# Main.net
KiCad netlist of a schematic drawn in Altium Designer
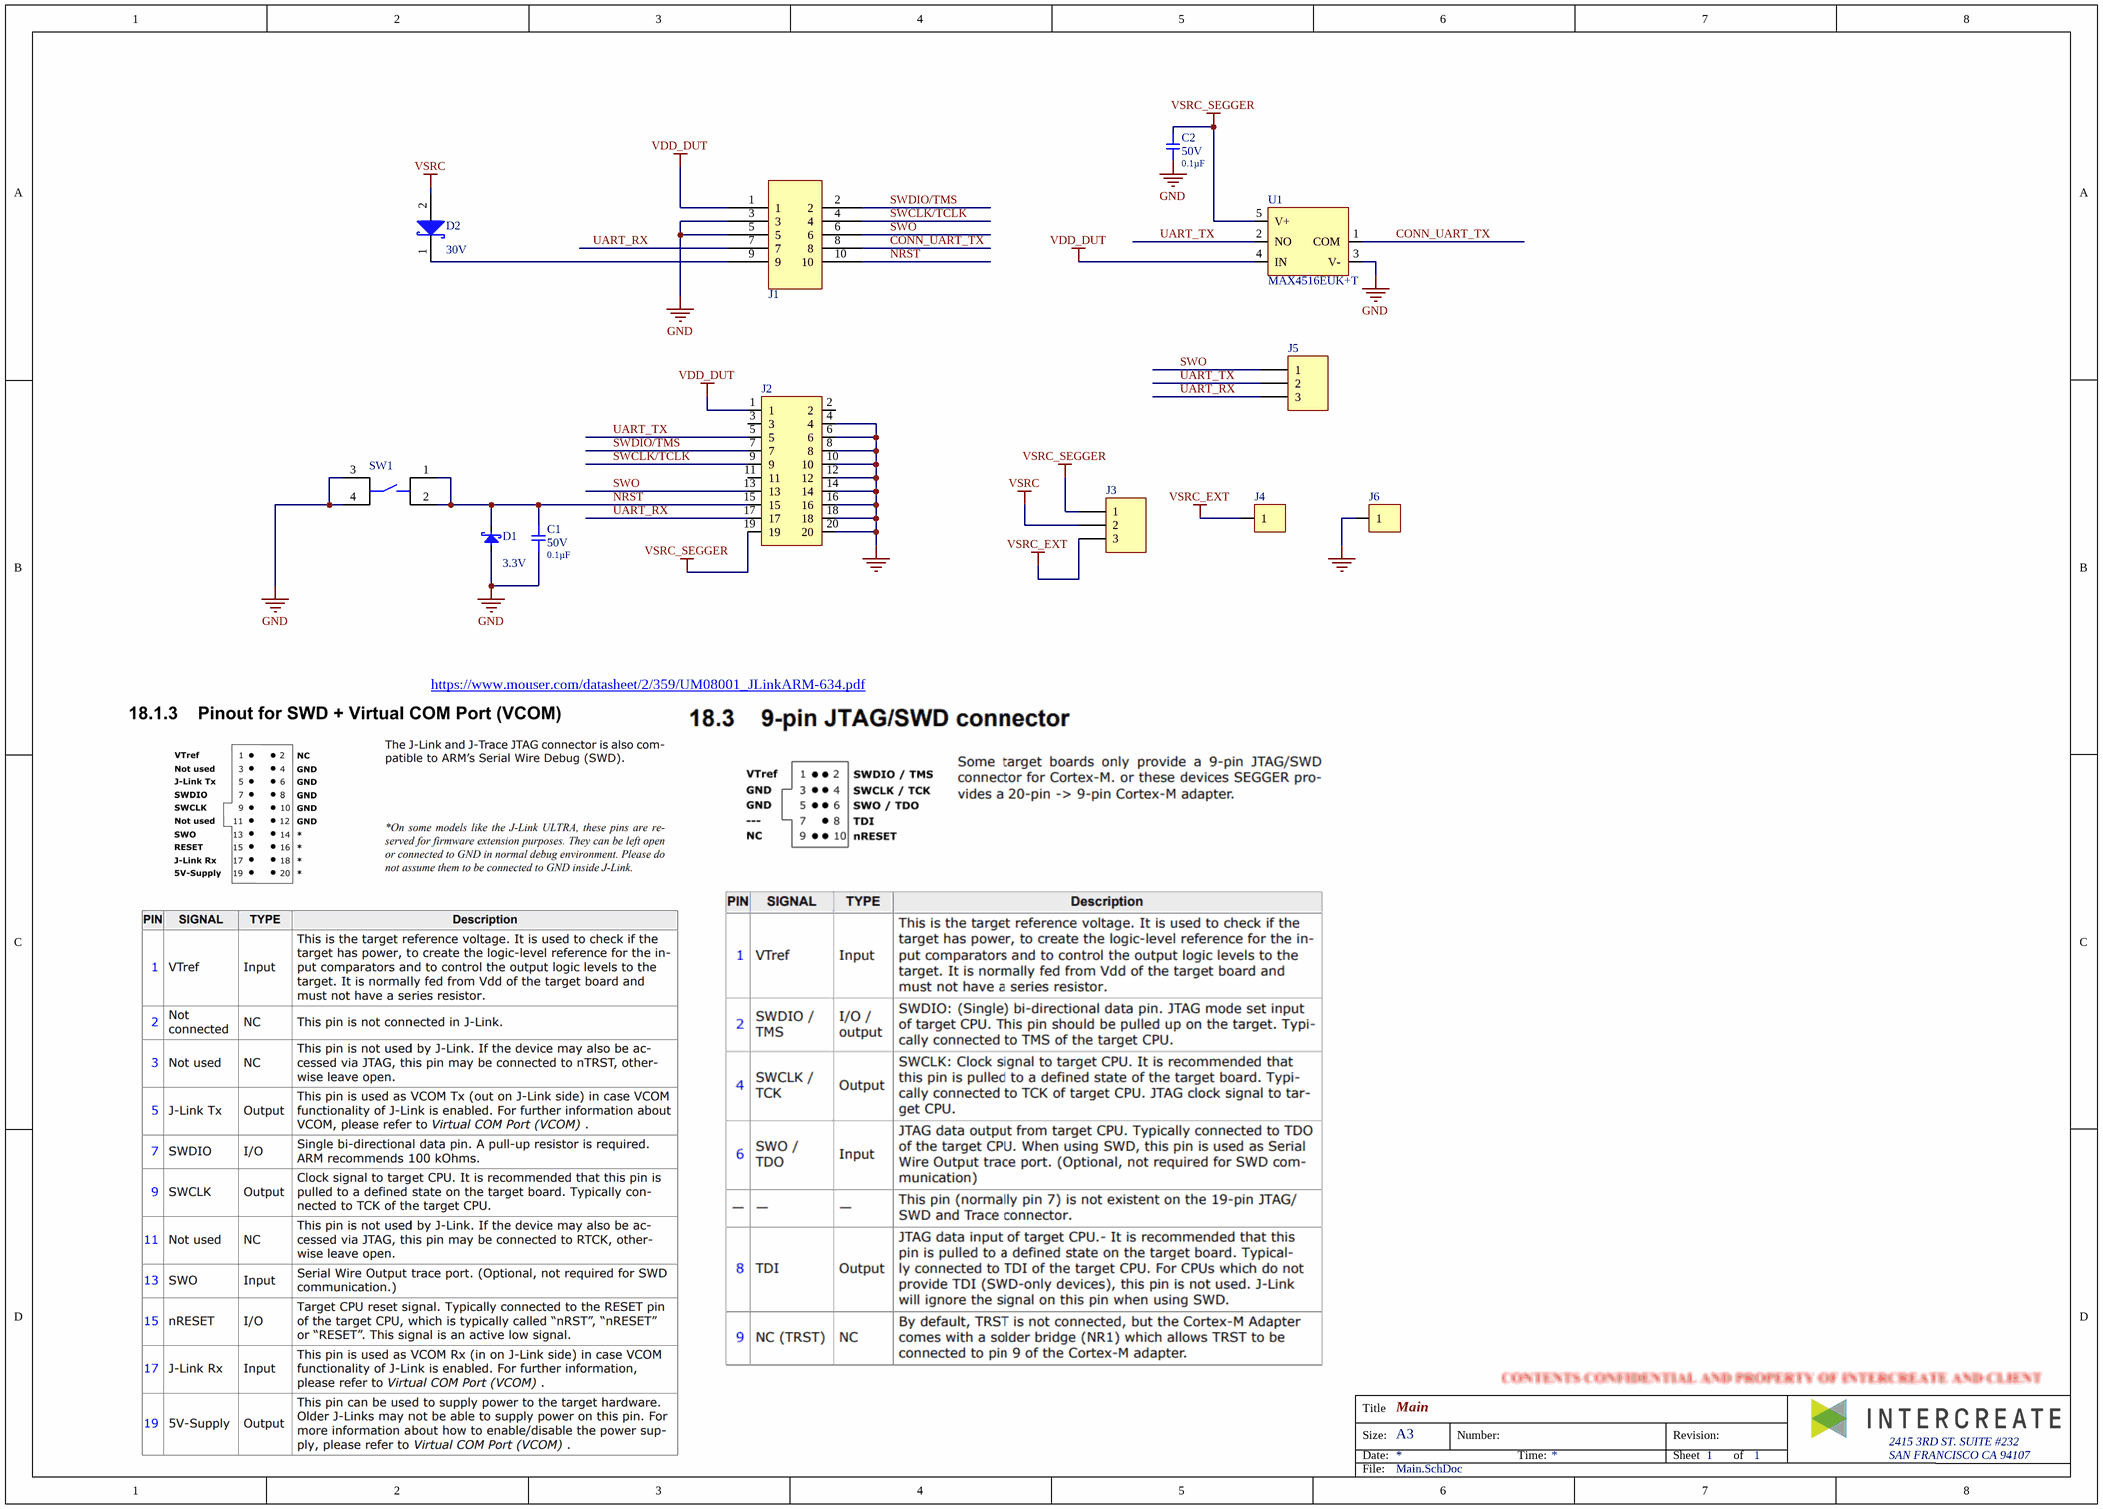
[diagram p0: Main.SchDoc]

(export (version "E")
  (design (tool "Eeschema 10.0.6"))
  (components
    (comp (ref "C1")
      (value "0.1µF")
      (footprint "CAP-0402")
      (description "CAP CER 0.1UF 50V X7R 0402 10%")
      (fields
        (field (name "TOLERANCE") "10%")
        (field (name "VOLTAGE RATING") "50V")
        (field (name "Comment") "GCM155R71H104KE02D")
      )
      (libsource (lib "intercreate") (part "CAP-0.1uF-50V-0402"))
    )
    (comp (ref "C2")
      (value "0.1µF")
      (footprint "CAP-0402")
      (description "CAP CER 0.1UF 50V X7R 0402 10%")
      (fields
        (field (name "TOLERANCE") "10%")
        (field (name "VOLTAGE RATING") "50V")
        (field (name "Comment") "GCM155R71H104KE02D")
      )
      (libsource (lib "intercreate") (part "CAP-0.1uF-50V-0402"))
    )
    (comp (ref "D1")
      (value "CPDQ3V3U-HF")
      (footprint "DIODE-SOD923f")
      (description "TVS DIODE 3.3V 10.4V SOD923F")
      (fields (field (name "REVERSE STANDOFF VOLTAGE") "3.3V"))
      (libsource (lib "intercreate") (part "DIODE-TVS-3.3V-SOD923F"))
    )
    (comp (ref "D2")
      (value "PMEG3010EP,115")
      (footprint "DIODE-SOD128")
      (description "DIODE SCHOTTKY 30V 1A SOD128")
      (fields (field (name "BASE PART NUMBER") "PMEG3010") (field (name "REVERSE VOLTAGE") "30V"))
      (libsource (lib "diodes") (part "DIODE-SCHOTTKY-30V-1A-SOD128"))
    )
    (comp (ref "J1")
      (value "FTSH-105-01-L-DV-K")
      (footprint "HDR-V-2X5-M")
      (description "CONN HEADER 10 POS DUAL .05\" SMD")
      (fields (field (name "MANUFACTURER") "Samtec"))
      (libsource (lib "intercreate") (part "HDR-V-2X5-M-JTAG"))
    )
    (comp (ref "J2")
      (value "SFH11-PBPC-D10-ST-BK")
      (footprint "HDR-V-2X10-F-2.54MM")
      (description "20 Position Header Connector 0.100\" (2.54mm) Through Hole Gold")
      (libsource (lib "intercreate") (part "HDR-V-2X10-F-2.54MM"))
    )
    (comp (ref "J3")
      (value "61300311121")
      (footprint "HDR-V-1X3")
      (description "Header, 3-Pin, 0.1\"")
      (fields (field (name "MANUFACTURER") "Wurth Electronics") (field (name "PUBLISHER") "Altium Limited"))
      (libsource (lib "intercreate") (part "HDR-V-1X3-M"))
    )
    (comp (ref "J4")
      (value "75160-101-01LF")
      (footprint "HDR-V-1X1-M")
      (libsource (lib "intercreate") (part "HDR-V-1X1-M"))
    )
    (comp (ref "J5")
      (value "61300311121")
      (footprint "HDR-V-1X3")
      (description "Header, 3-Pin, 0.1\"")
      (fields (field (name "MANUFACTURER") "Wurth Electronics") (field (name "PUBLISHER") "Altium Limited"))
      (libsource (lib "intercreate") (part "HDR-V-1X3-M"))
    )
    (comp (ref "J6")
      (value "75160-101-01LF")
      (footprint "HDR-V-1X1-M")
      (libsource (lib "intercreate") (part "HDR-V-1X1-M"))
    )
    (comp (ref "SW1")
      (value "PTS645SK50SMTR92 LFS")
      (footprint "BTN-SPST-PTS645SK50SMTR92")
      (description "C & K COMPONENTS - PTS645SK50SMTR92LFS - SWITCH, SPST, 0.05A, 12VDC, SMD, 5MM")
      (libsource (lib "intercreate") (part "BTN-SPST-PTS645SK50SMTR92"))
    )
    (comp (ref "U1")
      (value "MAX4516EUK+T")
      (footprint "IC-SOT-23-5")
      (description "MAX4516 Series SPST-NO 6V 20 Ohm SMT Analog Switch - SOT-23")
      (libsource (lib "intercreate") (part "IC-SW-MAX4516"))
    )
  )
  (nets
    (net (code "1") (name "/CONN_UART_TX") (class "Default")
      (node (ref "J1") (pin "8") (pinfunction "8_8") (pintype "passive"))
      (node (ref "U1") (pin "1") (pinfunction "COM_1") (pintype "passive"))
    )
    (net (code "2") (name "/NRST") (class "Default")
      (node (ref "C1") (pin "2") (pinfunction "2_2") (pintype "passive"))
      (node (ref "D1") (pin "1") (pinfunction "K_1") (pintype "passive"))
      (node (ref "J1") (pin "10") (pinfunction "10_10") (pintype "passive"))
      (node (ref "J2") (pin "15") (pinfunction "15_15") (pintype "passive"))
      (node (ref "SW1") (pin "1") (pinfunction "1_1") (pintype "passive"))
      (node (ref "SW1") (pin "2") (pinfunction "2_2") (pintype "passive"))
    )
    (net (code "3") (name "/SWCLK{slash}TCLK") (class "Default")
      (node (ref "J1") (pin "4") (pinfunction "4_4") (pintype "passive"))
      (node (ref "J2") (pin "9") (pinfunction "9_9") (pintype "passive"))
    )
    (net (code "4") (name "/SWDIO{slash}TMS") (class "Default")
      (node (ref "J1") (pin "2") (pinfunction "2_2") (pintype "passive"))
      (node (ref "J2") (pin "7") (pinfunction "7_7") (pintype "passive"))
    )
    (net (code "5") (name "/SWO") (class "Default")
      (node (ref "J1") (pin "6") (pinfunction "6_6") (pintype "passive"))
      (node (ref "J2") (pin "13") (pinfunction "13_13") (pintype "passive"))
      (node (ref "J5") (pin "1") (pinfunction "1_1") (pintype "passive"))
    )
    (net (code "6") (name "/UART_RX") (class "Default")
      (node (ref "J1") (pin "7") (pinfunction "7_7") (pintype "passive"))
      (node (ref "J2") (pin "17") (pinfunction "17_17") (pintype "passive"))
      (node (ref "J5") (pin "3") (pinfunction "3_3") (pintype "passive"))
    )
    (net (code "7") (name "/UART_TX") (class "Default")
      (node (ref "J2") (pin "5") (pinfunction "5_5") (pintype "passive"))
      (node (ref "J5") (pin "2") (pinfunction "2_2") (pintype "passive"))
      (node (ref "U1") (pin "2") (pinfunction "NO_2") (pintype "passive"))
    )
    (net (code "8") (name "GND") (class "Default")
      (node (ref "C1") (pin "1") (pinfunction "1_1") (pintype "passive"))
      (node (ref "C2") (pin "1") (pinfunction "1_1") (pintype "passive"))
      (node (ref "D1") (pin "2") (pinfunction "A_2") (pintype "passive"))
      (node (ref "J1") (pin "3") (pinfunction "3_3") (pintype "passive"))
      (node (ref "J1") (pin "5") (pinfunction "5_5") (pintype "passive"))
      (node (ref "J2") (pin "10") (pinfunction "10_10") (pintype "passive"))
      (node (ref "J2") (pin "12") (pinfunction "12_12") (pintype "passive"))
      (node (ref "J2") (pin "14") (pinfunction "14_14") (pintype "passive"))
      (node (ref "J2") (pin "16") (pinfunction "16_16") (pintype "passive"))
      (node (ref "J2") (pin "18") (pinfunction "18_18") (pintype "passive"))
      (node (ref "J2") (pin "20") (pinfunction "20_20") (pintype "passive"))
      (node (ref "J2") (pin "4") (pinfunction "4_4") (pintype "passive"))
      (node (ref "J2") (pin "6") (pinfunction "6_6") (pintype "passive"))
      (node (ref "J2") (pin "8") (pinfunction "8_8") (pintype "passive"))
      (node (ref "J6") (pin "1") (pinfunction "1_1") (pintype "passive"))
      (node (ref "SW1") (pin "3") (pinfunction "3_3") (pintype "passive"))
      (node (ref "SW1") (pin "4") (pinfunction "4_4") (pintype "passive"))
      (node (ref "U1") (pin "3") (pinfunction "V-_3") (pintype "passive"))
    )
    (net (code "9") (name "Net-(D2-K)") (class "Default")
      (node (ref "D2") (pin "1") (pinfunction "K_1") (pintype "passive"))
      (node (ref "J1") (pin "9") (pinfunction "9_9") (pintype "passive"))
    )
    (net (code "10") (name "VDD_DUT") (class "Default")
      (node (ref "J1") (pin "1") (pinfunction "1_1") (pintype "passive"))
      (node (ref "J2") (pin "1") (pinfunction "1_1") (pintype "passive"))
      (node (ref "U1") (pin "4") (pinfunction "IN_4") (pintype "passive"))
    )
    (net (code "11") (name "VSRC") (class "Default")
      (node (ref "D2") (pin "2") (pinfunction "A_2") (pintype "passive"))
      (node (ref "J3") (pin "2") (pinfunction "2_2") (pintype "passive"))
    )
    (net (code "12") (name "VSRC_EXT") (class "Default")
      (node (ref "J3") (pin "3") (pinfunction "3_3") (pintype "passive"))
      (node (ref "J4") (pin "1") (pinfunction "1_1") (pintype "passive"))
    )
    (net (code "13") (name "VSRC_SEGGER") (class "Default")
      (node (ref "C2") (pin "2") (pinfunction "2_2") (pintype "passive"))
      (node (ref "J2") (pin "19") (pinfunction "19_19") (pintype "passive"))
      (node (ref "J3") (pin "1") (pinfunction "1_1") (pintype "passive"))
      (node (ref "U1") (pin "5") (pinfunction "V+_5") (pintype "passive"))
    )
    (net (code "14") (name "unconnected-(J2-Pad2)") (class "Default")
      (node (ref "J2") (pin "2") (pinfunction "2_2") (pintype "passive"))
    )
    (net (code "15") (name "unconnected-(J2-Pad3)") (class "Default")
      (node (ref "J2") (pin "3") (pinfunction "3_3") (pintype "passive"))
    )
    (net (code "16") (name "unconnected-(J2-Pad11)") (class "Default")
      (node (ref "J2") (pin "11") (pinfunction "11_11") (pintype "passive"))
    )
  )
)
